# WIFI-Relay_v0_2.net
KiCad netlist of a schematic drawn in EAGLE
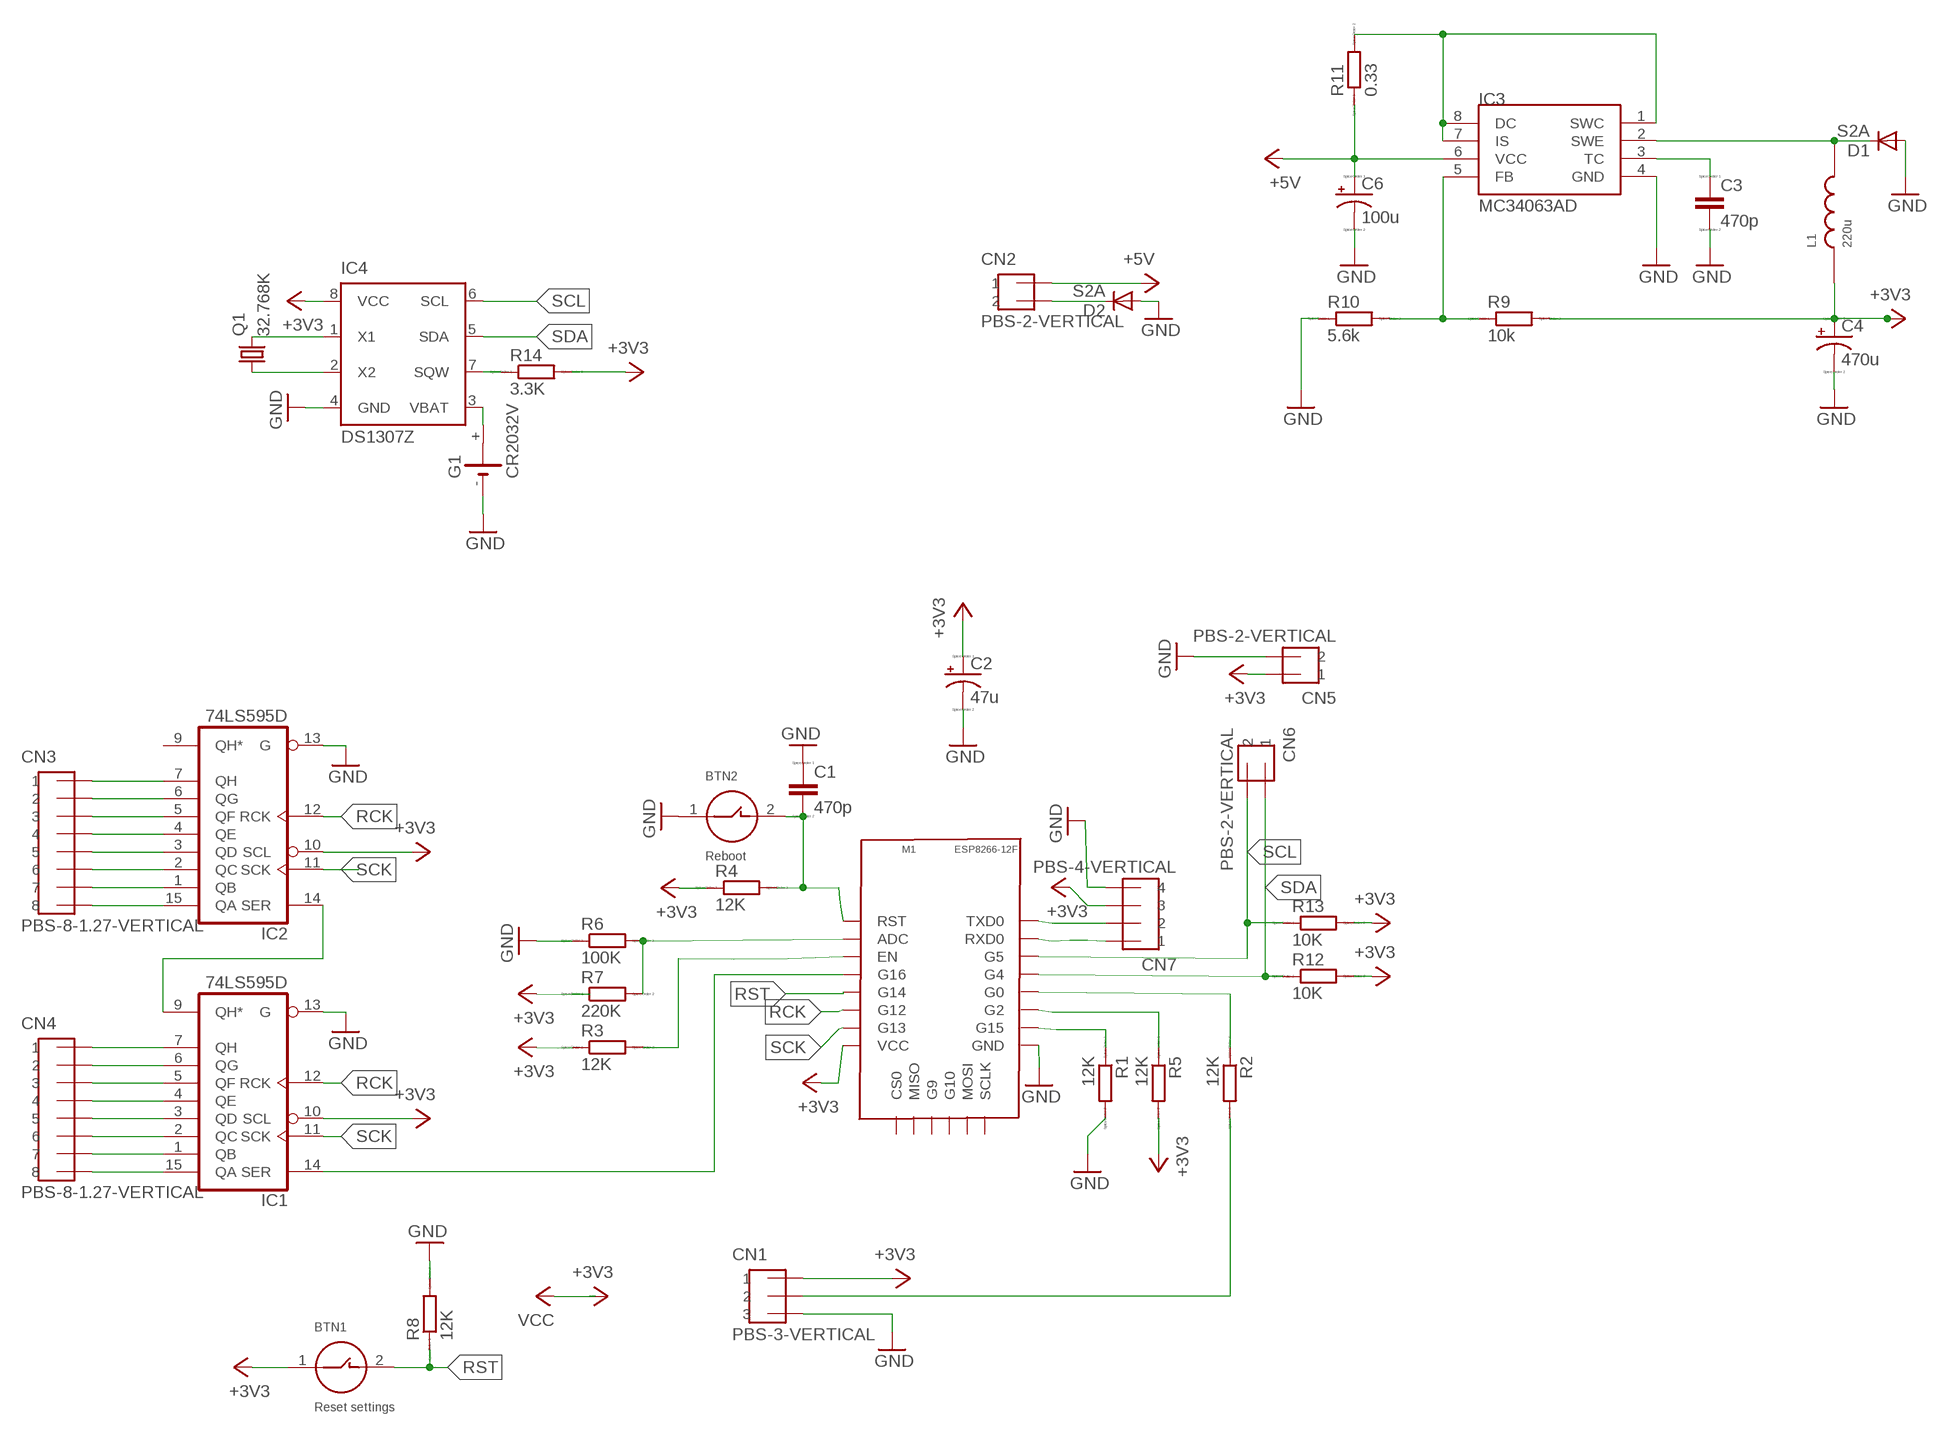
[diagram p0: schematic, sheet 1]

(export (version "E")
  (design (tool "Eeschema 10.0.6"))
  (components
    (comp (ref "BTN1")
      (value "Reset settings")
      (footprint "eagle-import:BTN-6X4-SMD")
      (libsource (lib "eagle-import") (part "BTN-6X4-SMD"))
    )
    (comp (ref "BTN2")
      (value "Reboot")
      (footprint "eagle-import:BTN-6X4-SMD")
      (libsource (lib "eagle-import") (part "BTN-6X4-SMD"))
    )
    (comp (ref "C1")
      (value "470p")
      (footprint "eagle-import:C0603")
      (libsource (lib "eagle-import") (part "CC0603"))
    )
    (comp (ref "C2")
      (value "47u")
      (footprint "eagle-import:CT3216")
      (libsource (lib "eagle-import") (part "CPOL-USCT3216"))
    )
    (comp (ref "C3")
      (value "470p")
      (footprint "eagle-import:C0603")
      (libsource (lib "eagle-import") (part "CC0603"))
    )
    (comp (ref "C4")
      (value "470u")
      (footprint "eagle-import:D_7343-31W")
      (libsource (lib "eagle-import") (part "CPOL-USD/7343-31W"))
    )
    (comp (ref "C6")
      (value "100u")
      (footprint "eagle-import:D_7343-31W")
      (libsource (lib "eagle-import") (part "CPOL-USD/7343-31W"))
    )
    (comp (ref "CN1")
      (value "PBS-3-VERTICAL")
      (footprint "eagle-import:PBS-3-VERTICAL")
      (libsource (lib "eagle-import") (part "PBS-3-VERTICAL"))
    )
    (comp (ref "CN2")
      (value "PBS-2-VERTICAL")
      (footprint "eagle-import:PBS-2-VERTICAL")
      (libsource (lib "eagle-import") (part "PBS-2-VERTICAL"))
    )
    (comp (ref "CN3")
      (value "PBS-8-1.27-VERTICAL")
      (footprint "eagle-import:PBS-8-1.27-VERTICAL")
      (libsource (lib "eagle-import") (part "PBS-8-1.27-VERTICAL"))
    )
    (comp (ref "CN4")
      (value "PBS-8-1.27-VERTICAL")
      (footprint "eagle-import:PBS-8-1.27-VERTICAL")
      (libsource (lib "eagle-import") (part "PBS-8-1.27-VERTICAL"))
    )
    (comp (ref "CN5")
      (value "PBS-2-VERTICAL")
      (footprint "eagle-import:PBS-2-VERTICAL")
      (libsource (lib "eagle-import") (part "PBS-2-VERTICAL"))
    )
    (comp (ref "CN6")
      (value "PBS-2-VERTICAL")
      (footprint "eagle-import:PBS-2-VERTICAL")
      (libsource (lib "eagle-import") (part "PBS-2-VERTICAL"))
    )
    (comp (ref "CN7")
      (value "PBS-4-VERTICAL")
      (footprint "eagle-import:PBS-4-VERTICAL")
      (libsource (lib "eagle-import") (part "PBS-4-VERTICAL"))
    )
    (comp (ref "D1")
      (value "S2A")
      (footprint "eagle-import:DO214AA")
      (fields (field (name "MF") "Fairchild"))
      (libsource (lib "eagle-import") (part "S2A"))
    )
    (comp (ref "D2")
      (value "S2A")
      (footprint "eagle-import:DO214AA")
      (fields (field (name "MF") "Fairchild"))
      (libsource (lib "eagle-import") (part "S2A"))
    )
    (comp (ref "G1")
      (value "CR2032V")
      (footprint "eagle-import:CR2032V")
      (libsource (lib "eagle-import") (part "CR2032V"))
    )
    (comp (ref "IC1")
      (value "74LS595D")
      (footprint "eagle-import:SO16")
      (libsource (lib "eagle-import") (part "74595DLS"))
    )
    (comp (ref "IC2")
      (value "74LS595D")
      (footprint "eagle-import:SO16")
      (libsource (lib "eagle-import") (part "74595DLS"))
    )
    (comp (ref "IC3")
      (value "MC34063AD")
      (footprint "eagle-import:SOIC8")
      (libsource (lib "eagle-import") (part "MC34063AD"))
    )
    (comp (ref "IC4")
      (value "DS1307Z")
      (footprint "eagle-import:SOIC8")
      (libsource (lib "eagle-import") (part "DS1307Z"))
    )
    (comp (ref "L1")
      (value "220u")
      (footprint "eagle-import:INDUCTOR-5-10")
      (libsource (lib "eagle-import") (part "INDUCTOR-5-10"))
    )
    (comp (ref "M1")
      (value "ESP8266-12F")
      (footprint "eagle-import:ESP8266-12F")
      (libsource (lib "eagle-import") (part "ESP8266-12F"))
    )
    (comp (ref "Q1")
      (value "32.768K")
      (footprint "eagle-import:TC38H")
      (libsource (lib "eagle-import") (part "CRYSTALTC38H"))
    )
    (comp (ref "R1")
      (value "12K")
      (footprint "eagle-import:R0603")
      (libsource (lib "eagle-import") (part "RR0603"))
    )
    (comp (ref "R2")
      (value "12K")
      (footprint "eagle-import:R0603")
      (libsource (lib "eagle-import") (part "RR0603"))
    )
    (comp (ref "R3")
      (value "12K")
      (footprint "eagle-import:R0603")
      (libsource (lib "eagle-import") (part "RR0603"))
    )
    (comp (ref "R4")
      (value "12K")
      (footprint "eagle-import:R0603")
      (libsource (lib "eagle-import") (part "RR0603"))
    )
    (comp (ref "R5")
      (value "12K")
      (footprint "eagle-import:R0603")
      (libsource (lib "eagle-import") (part "RR0603"))
    )
    (comp (ref "R6")
      (value "100K")
      (footprint "eagle-import:R0603")
      (libsource (lib "eagle-import") (part "RR0603"))
    )
    (comp (ref "R7")
      (value "220K")
      (footprint "eagle-import:R0603")
      (libsource (lib "eagle-import") (part "RR0603"))
    )
    (comp (ref "R8")
      (value "12K")
      (footprint "eagle-import:R0603")
      (libsource (lib "eagle-import") (part "RR0603"))
    )
    (comp (ref "R9")
      (value "10k")
      (footprint "eagle-import:R0603")
      (libsource (lib "eagle-import") (part "RR0603"))
    )
    (comp (ref "R10")
      (value "5.6k")
      (footprint "eagle-import:R0603")
      (libsource (lib "eagle-import") (part "RR0603"))
    )
    (comp (ref "R11")
      (value "0.33")
      (footprint "eagle-import:R0603")
      (libsource (lib "eagle-import") (part "RR0603"))
    )
    (comp (ref "R12")
      (value "10K")
      (footprint "eagle-import:R0603")
      (libsource (lib "eagle-import") (part "RR0603"))
    )
    (comp (ref "R13")
      (value "10K")
      (footprint "eagle-import:R0603")
      (libsource (lib "eagle-import") (part "RR0603"))
    )
    (comp (ref "R14")
      (value "3.3K")
      (footprint "eagle-import:R0603")
      (libsource (lib "eagle-import") (part "RR0603"))
    )
  )
  (nets
    (net (code "1") (name "+3V3") (class "Default")
      (node (ref "BTN1") (pin "1") (pinfunction "1_1") (pintype "bidirectional"))
      (node (ref "C2") (pin "-") (pinfunction "+_-") (pintype "passive"))
      (node (ref "C4") (pin "+") (pinfunction "+_+") (pintype "passive"))
      (node (ref "CN1") (pin "P$1") (pinfunction "1_P$1") (pintype "bidirectional"))
      (node (ref "CN5") (pin "P$1") (pinfunction "1_P$1") (pintype "bidirectional"))
      (node (ref "CN7") (pin "P$3") (pinfunction "3_P$3") (pintype "bidirectional"))
      (node (ref "IC1") (pin "10") (pinfunction "SCL_10") (pintype "input"))
      (node (ref "IC2") (pin "10") (pinfunction "SCL_10") (pintype "input"))
      (node (ref "IC4") (pin "8") (pinfunction "VCC_8") (pintype "power_in"))
      (node (ref "L1") (pin "P$1") (pinfunction "1_P$1") (pintype "bidirectional"))
      (node (ref "M1") (pin "VCC") (pinfunction "VCC_VCC") (pintype "power_in"))
      (node (ref "R12") (pin "2") (pinfunction "2_2") (pintype "passive"))
      (node (ref "R13") (pin "2") (pinfunction "2_2") (pintype "passive"))
      (node (ref "R14") (pin "2") (pinfunction "2_2") (pintype "passive"))
      (node (ref "R3") (pin "1") (pinfunction "1_1") (pintype "passive"))
      (node (ref "R4") (pin "1") (pinfunction "1_1") (pintype "passive"))
      (node (ref "R5") (pin "2") (pinfunction "2_2") (pintype "passive"))
      (node (ref "R7") (pin "1") (pinfunction "1_1") (pintype "passive"))
      (node (ref "R9") (pin "2") (pinfunction "2_2") (pintype "passive"))
    )
    (net (code "2") (name "+5V") (class "Default")
      (node (ref "C6") (pin "+") (pinfunction "+_+") (pintype "passive"))
      (node (ref "CN2") (pin "P$1") (pinfunction "1_P$1") (pintype "bidirectional"))
      (node (ref "IC3") (pin "6") (pinfunction "VCC_6") (pintype "passive"))
      (node (ref "R11") (pin "1") (pinfunction "1_1") (pintype "passive"))
    )
    (net (code "3") (name "/N$24") (class "Default")
      (node (ref "BTN2") (pin "2") (pinfunction "2_2") (pintype "bidirectional"))
      (node (ref "C1") (pin "2") (pinfunction "2_2") (pintype "passive"))
      (node (ref "M1") (pin "RST") (pinfunction "RST_RST") (pintype "bidirectional"))
      (node (ref "R4") (pin "2") (pinfunction "2_2") (pintype "passive"))
    )
    (net (code "4") (name "GND") (class "Default")
      (node (ref "BTN2") (pin "1") (pinfunction "1_1") (pintype "bidirectional"))
      (node (ref "C1") (pin "1") (pinfunction "1_1") (pintype "passive"))
      (node (ref "C2") (pin "+") (pinfunction "-_+") (pintype "passive"))
      (node (ref "C3") (pin "2") (pinfunction "2_2") (pintype "passive"))
      (node (ref "C4") (pin "-") (pinfunction "-_-") (pintype "passive"))
      (node (ref "C6") (pin "-") (pinfunction "-_-") (pintype "passive"))
      (node (ref "CN1") (pin "P$3") (pinfunction "3_P$3") (pintype "bidirectional"))
      (node (ref "CN5") (pin "P$2") (pinfunction "2_P$2") (pintype "bidirectional"))
      (node (ref "CN7") (pin "P$4") (pinfunction "4_P$4") (pintype "bidirectional"))
      (node (ref "D1") (pin "A") (pinfunction "A_A") (pintype "passive"))
      (node (ref "D2") (pin "A") (pinfunction "A_A") (pintype "passive"))
      (node (ref "G1") (pin "-") (pinfunction "-_-") (pintype "passive"))
      (node (ref "IC1") (pin "13") (pinfunction "G_13") (pintype "input"))
      (node (ref "IC2") (pin "13") (pinfunction "G_13") (pintype "input"))
      (node (ref "IC3") (pin "4") (pinfunction "GND_4") (pintype "passive"))
      (node (ref "IC4") (pin "4") (pinfunction "GND_4") (pintype "power_in"))
      (node (ref "M1") (pin "GND") (pinfunction "GND_GND") (pintype "power_in"))
      (node (ref "R1") (pin "2") (pinfunction "2_2") (pintype "passive"))
      (node (ref "R10") (pin "1") (pinfunction "1_1") (pintype "passive"))
      (node (ref "R6") (pin "1") (pinfunction "1_1") (pintype "passive"))
      (node (ref "R8") (pin "2") (pinfunction "2_2") (pintype "passive"))
    )
    (net (code "5") (name "Net-(CN1-2)") (class "Default")
      (node (ref "CN1") (pin "P$2") (pinfunction "2_P$2") (pintype "bidirectional"))
      (node (ref "R2") (pin "2") (pinfunction "2_2") (pintype "passive"))
    )
    (net (code "6") (name "Net-(CN2-2)") (class "Default")
      (node (ref "CN2") (pin "P$2") (pinfunction "2_P$2") (pintype "bidirectional"))
      (node (ref "D2") (pin "C") (pinfunction "C_C") (pintype "passive"))
    )
    (net (code "7") (name "Net-(CN3-1)") (class "Default")
      (node (ref "CN3") (pin "P$1") (pinfunction "1_P$1") (pintype "bidirectional"))
      (node (ref "IC2") (pin "7") (pinfunction "QH_7") (pintype "tri_state"))
    )
    (net (code "8") (name "Net-(CN3-2)") (class "Default")
      (node (ref "CN3") (pin "P$2") (pinfunction "2_P$2") (pintype "bidirectional"))
      (node (ref "IC2") (pin "6") (pinfunction "QG_6") (pintype "tri_state"))
    )
    (net (code "9") (name "Net-(CN3-3)") (class "Default")
      (node (ref "CN3") (pin "P$3") (pinfunction "3_P$3") (pintype "bidirectional"))
      (node (ref "IC2") (pin "5") (pinfunction "QF_5") (pintype "tri_state"))
    )
    (net (code "10") (name "Net-(CN3-4)") (class "Default")
      (node (ref "CN3") (pin "P$4") (pinfunction "4_P$4") (pintype "bidirectional"))
      (node (ref "IC2") (pin "4") (pinfunction "QE_4") (pintype "tri_state"))
    )
    (net (code "11") (name "Net-(CN3-5)") (class "Default")
      (node (ref "CN3") (pin "P$5") (pinfunction "5_P$5") (pintype "bidirectional"))
      (node (ref "IC2") (pin "3") (pinfunction "QD_3") (pintype "tri_state"))
    )
    (net (code "12") (name "Net-(CN3-6)") (class "Default")
      (node (ref "CN3") (pin "P$6") (pinfunction "6_P$6") (pintype "bidirectional"))
      (node (ref "IC2") (pin "2") (pinfunction "QC_2") (pintype "tri_state"))
    )
    (net (code "13") (name "Net-(CN3-7)") (class "Default")
      (node (ref "CN3") (pin "P$7") (pinfunction "7_P$7") (pintype "bidirectional"))
      (node (ref "IC2") (pin "1") (pinfunction "QB_1") (pintype "tri_state"))
    )
    (net (code "14") (name "Net-(CN3-8)") (class "Default")
      (node (ref "CN3") (pin "P$8") (pinfunction "8_P$8") (pintype "bidirectional"))
      (node (ref "IC2") (pin "15") (pinfunction "QA_15") (pintype "tri_state"))
    )
    (net (code "15") (name "Net-(CN4-1)") (class "Default")
      (node (ref "CN4") (pin "P$1") (pinfunction "1_P$1") (pintype "bidirectional"))
      (node (ref "IC1") (pin "7") (pinfunction "QH_7") (pintype "tri_state"))
    )
    (net (code "16") (name "Net-(CN4-2)") (class "Default")
      (node (ref "CN4") (pin "P$2") (pinfunction "2_P$2") (pintype "bidirectional"))
      (node (ref "IC1") (pin "6") (pinfunction "QG_6") (pintype "tri_state"))
    )
    (net (code "17") (name "Net-(CN4-3)") (class "Default")
      (node (ref "CN4") (pin "P$3") (pinfunction "3_P$3") (pintype "bidirectional"))
      (node (ref "IC1") (pin "5") (pinfunction "QF_5") (pintype "tri_state"))
    )
    (net (code "18") (name "Net-(CN4-4)") (class "Default")
      (node (ref "CN4") (pin "P$4") (pinfunction "4_P$4") (pintype "bidirectional"))
      (node (ref "IC1") (pin "4") (pinfunction "QE_4") (pintype "tri_state"))
    )
    (net (code "19") (name "Net-(CN4-5)") (class "Default")
      (node (ref "CN4") (pin "P$5") (pinfunction "5_P$5") (pintype "bidirectional"))
      (node (ref "IC1") (pin "3") (pinfunction "QD_3") (pintype "tri_state"))
    )
    (net (code "20") (name "Net-(CN4-6)") (class "Default")
      (node (ref "CN4") (pin "P$6") (pinfunction "6_P$6") (pintype "bidirectional"))
      (node (ref "IC1") (pin "2") (pinfunction "QC_2") (pintype "tri_state"))
    )
    (net (code "21") (name "Net-(CN4-7)") (class "Default")
      (node (ref "CN4") (pin "P$7") (pinfunction "7_P$7") (pintype "bidirectional"))
      (node (ref "IC1") (pin "1") (pinfunction "QB_1") (pintype "tri_state"))
    )
    (net (code "22") (name "Net-(CN4-8)") (class "Default")
      (node (ref "CN4") (pin "P$8") (pinfunction "8_P$8") (pintype "bidirectional"))
      (node (ref "IC1") (pin "15") (pinfunction "QA_15") (pintype "tri_state"))
    )
    (net (code "23") (name "Net-(CN7-1)") (class "Default")
      (node (ref "CN7") (pin "P$1") (pinfunction "1_P$1") (pintype "bidirectional"))
      (node (ref "M1") (pin "RXD0") (pinfunction "RXD0_RXD0") (pintype "bidirectional"))
    )
    (net (code "24") (name "Net-(CN7-2)") (class "Default")
      (node (ref "CN7") (pin "P$2") (pinfunction "2_P$2") (pintype "bidirectional"))
      (node (ref "M1") (pin "TXD0") (pinfunction "TXD0_TXD0") (pintype "bidirectional"))
    )
    (net (code "25") (name "Net-(IC1A-QH*)") (class "Default")
      (node (ref "IC1") (pin "9") (pinfunction "QH*_9") (pintype "tri_state"))
      (node (ref "IC2") (pin "14") (pinfunction "SER_14") (pintype "input"))
    )
    (net (code "26") (name "Net-(IC1A-SER)") (class "Default")
      (node (ref "IC1") (pin "14") (pinfunction "SER_14") (pintype "input"))
      (node (ref "M1") (pin "G16") (pinfunction "G16_G16") (pintype "bidirectional"))
    )
    (net (code "27") (name "Net-(IC3-DC)") (class "Default")
      (node (ref "IC3") (pin "1") (pinfunction "SWC_1") (pintype "passive"))
      (node (ref "IC3") (pin "7") (pinfunction "IS_7") (pintype "passive"))
      (node (ref "IC3") (pin "8") (pinfunction "DC_8") (pintype "passive"))
      (node (ref "R11") (pin "2") (pinfunction "2_2") (pintype "passive"))
    )
    (net (code "28") (name "Net-(IC3-FB)") (class "Default")
      (node (ref "IC3") (pin "5") (pinfunction "FB_5") (pintype "passive"))
      (node (ref "R10") (pin "2") (pinfunction "2_2") (pintype "passive"))
      (node (ref "R9") (pin "1") (pinfunction "1_1") (pintype "passive"))
    )
    (net (code "29") (name "Net-(IC3-SWE)") (class "Default")
      (node (ref "D1") (pin "C") (pinfunction "C_C") (pintype "passive"))
      (node (ref "IC3") (pin "2") (pinfunction "SWE_2") (pintype "passive"))
      (node (ref "L1") (pin "P$2") (pinfunction "P$2_P$2") (pintype "bidirectional"))
    )
    (net (code "30") (name "Net-(IC3-TC)") (class "Default")
      (node (ref "C3") (pin "1") (pinfunction "1_1") (pintype "passive"))
      (node (ref "IC3") (pin "3") (pinfunction "TC_3") (pintype "passive"))
    )
    (net (code "31") (name "Net-(IC4-SQW)") (class "Default")
      (node (ref "IC4") (pin "7") (pinfunction "SQW_7") (pintype "open_collector"))
      (node (ref "R14") (pin "1") (pinfunction "1_1") (pintype "passive"))
    )
    (net (code "32") (name "Net-(IC4-VBAT)") (class "Default")
      (node (ref "G1") (pin "+") (pinfunction "+_+") (pintype "passive"))
      (node (ref "IC4") (pin "3") (pinfunction "VBAT_3") (pintype "passive"))
    )
    (net (code "33") (name "Net-(IC4-X1)") (class "Default")
      (node (ref "IC4") (pin "1") (pinfunction "X1_1") (pintype "input"))
      (node (ref "Q1") (pin "2") (pinfunction "2_2") (pintype "passive"))
    )
    (net (code "34") (name "Net-(IC4-X2)") (class "Default")
      (node (ref "IC4") (pin "2") (pinfunction "X2_2") (pintype "output"))
      (node (ref "Q1") (pin "1") (pinfunction "1_1") (pintype "passive"))
    )
    (net (code "35") (name "Net-(M1-PadADC)") (class "Default")
      (node (ref "M1") (pin "ADC") (pinfunction "ADC_ADC") (pintype "bidirectional"))
      (node (ref "R6") (pin "2") (pinfunction "2_2") (pintype "passive"))
      (node (ref "R7") (pin "2") (pinfunction "2_2") (pintype "passive"))
    )
    (net (code "36") (name "Net-(M1-PadEN)") (class "Default")
      (node (ref "M1") (pin "EN") (pinfunction "EN_EN") (pintype "bidirectional"))
      (node (ref "R3") (pin "2") (pinfunction "2_2") (pintype "passive"))
    )
    (net (code "37") (name "Net-(M1-PadG0)") (class "Default")
      (node (ref "M1") (pin "G0") (pinfunction "G0_G0") (pintype "bidirectional"))
      (node (ref "R2") (pin "1") (pinfunction "1_1") (pintype "passive"))
    )
    (net (code "38") (name "Net-(M1-PadG2)") (class "Default")
      (node (ref "M1") (pin "G2") (pinfunction "G2_G2") (pintype "bidirectional"))
      (node (ref "R5") (pin "1") (pinfunction "1_1") (pintype "passive"))
    )
    (net (code "39") (name "Net-(M1-PadG15)") (class "Default")
      (node (ref "M1") (pin "G15") (pinfunction "G15_G15") (pintype "bidirectional"))
      (node (ref "R1") (pin "1") (pinfunction "1_1") (pintype "passive"))
    )
    (net (code "40") (name "RCK") (class "Default")
      (node (ref "IC1") (pin "12") (pinfunction "RCK_12") (pintype "input"))
      (node (ref "IC2") (pin "12") (pinfunction "RCK_12") (pintype "input"))
      (node (ref "M1") (pin "G12") (pinfunction "G12_G12") (pintype "bidirectional"))
    )
    (net (code "41") (name "RST") (class "Default")
      (node (ref "BTN1") (pin "2") (pinfunction "2_2") (pintype "bidirectional"))
      (node (ref "M1") (pin "G14") (pinfunction "G14_G14") (pintype "bidirectional"))
      (node (ref "R8") (pin "1") (pinfunction "1_1") (pintype "passive"))
    )
    (net (code "42") (name "SCK") (class "Default")
      (node (ref "IC1") (pin "11") (pinfunction "SCK_11") (pintype "input"))
      (node (ref "IC2") (pin "11") (pinfunction "SCK_11") (pintype "input"))
      (node (ref "M1") (pin "G13") (pinfunction "G13_G13") (pintype "bidirectional"))
    )
    (net (code "43") (name "SCL") (class "Default")
      (node (ref "CN6") (pin "P$2") (pinfunction "2_P$2") (pintype "bidirectional"))
      (node (ref "IC4") (pin "6") (pinfunction "SCL_6") (pintype "input"))
      (node (ref "M1") (pin "G5") (pinfunction "G5_G5") (pintype "bidirectional"))
      (node (ref "R13") (pin "1") (pinfunction "1_1") (pintype "passive"))
    )
    (net (code "44") (name "SDA") (class "Default")
      (node (ref "CN6") (pin "P$1") (pinfunction "1_P$1") (pintype "bidirectional"))
      (node (ref "IC4") (pin "5") (pinfunction "SDA_5") (pintype "bidirectional"))
      (node (ref "M1") (pin "G4") (pinfunction "G4_G4") (pintype "bidirectional"))
      (node (ref "R12") (pin "1") (pinfunction "1_1") (pintype "passive"))
    )
    (net (code "45") (name "unconnected-(G1-+-Pad+@1)") (class "Default")
      (node (ref "G1") (pin "+@1") (pinfunction "+_+@1") (pintype "passive"))
    )
    (net (code "46") (name "unconnected-(IC2A-QH*-Pad9)") (class "Default")
      (node (ref "IC2") (pin "9") (pinfunction "QH*_9") (pintype "tri_state"))
    )
    (net (code "47") (name "unconnected-(M1-PadCS0)") (class "Default")
      (node (ref "M1") (pin "CS0") (pinfunction "CS0_CS0") (pintype "bidirectional"))
    )
    (net (code "48") (name "unconnected-(M1-PadG9)") (class "Default")
      (node (ref "M1") (pin "G9") (pinfunction "G9_G9") (pintype "bidirectional"))
    )
    (net (code "49") (name "unconnected-(M1-PadG10)") (class "Default")
      (node (ref "M1") (pin "G10") (pinfunction "G10_G10") (pintype "bidirectional"))
    )
    (net (code "50") (name "unconnected-(M1-PadMISO)") (class "Default")
      (node (ref "M1") (pin "MISO") (pinfunction "MISO_MISO") (pintype "bidirectional"))
    )
    (net (code "51") (name "unconnected-(M1-PadMOSI)") (class "Default")
      (node (ref "M1") (pin "MOSI") (pinfunction "MOSI_MOSI") (pintype "bidirectional"))
    )
    (net (code "52") (name "unconnected-(M1-PadSCLK)") (class "Default")
      (node (ref "M1") (pin "SCLK") (pinfunction "SCLK_SCLK") (pintype "bidirectional"))
    )
  )
)
